# IO_and_MCU.net
KiCad netlist of a schematic drawn in Altium Designer
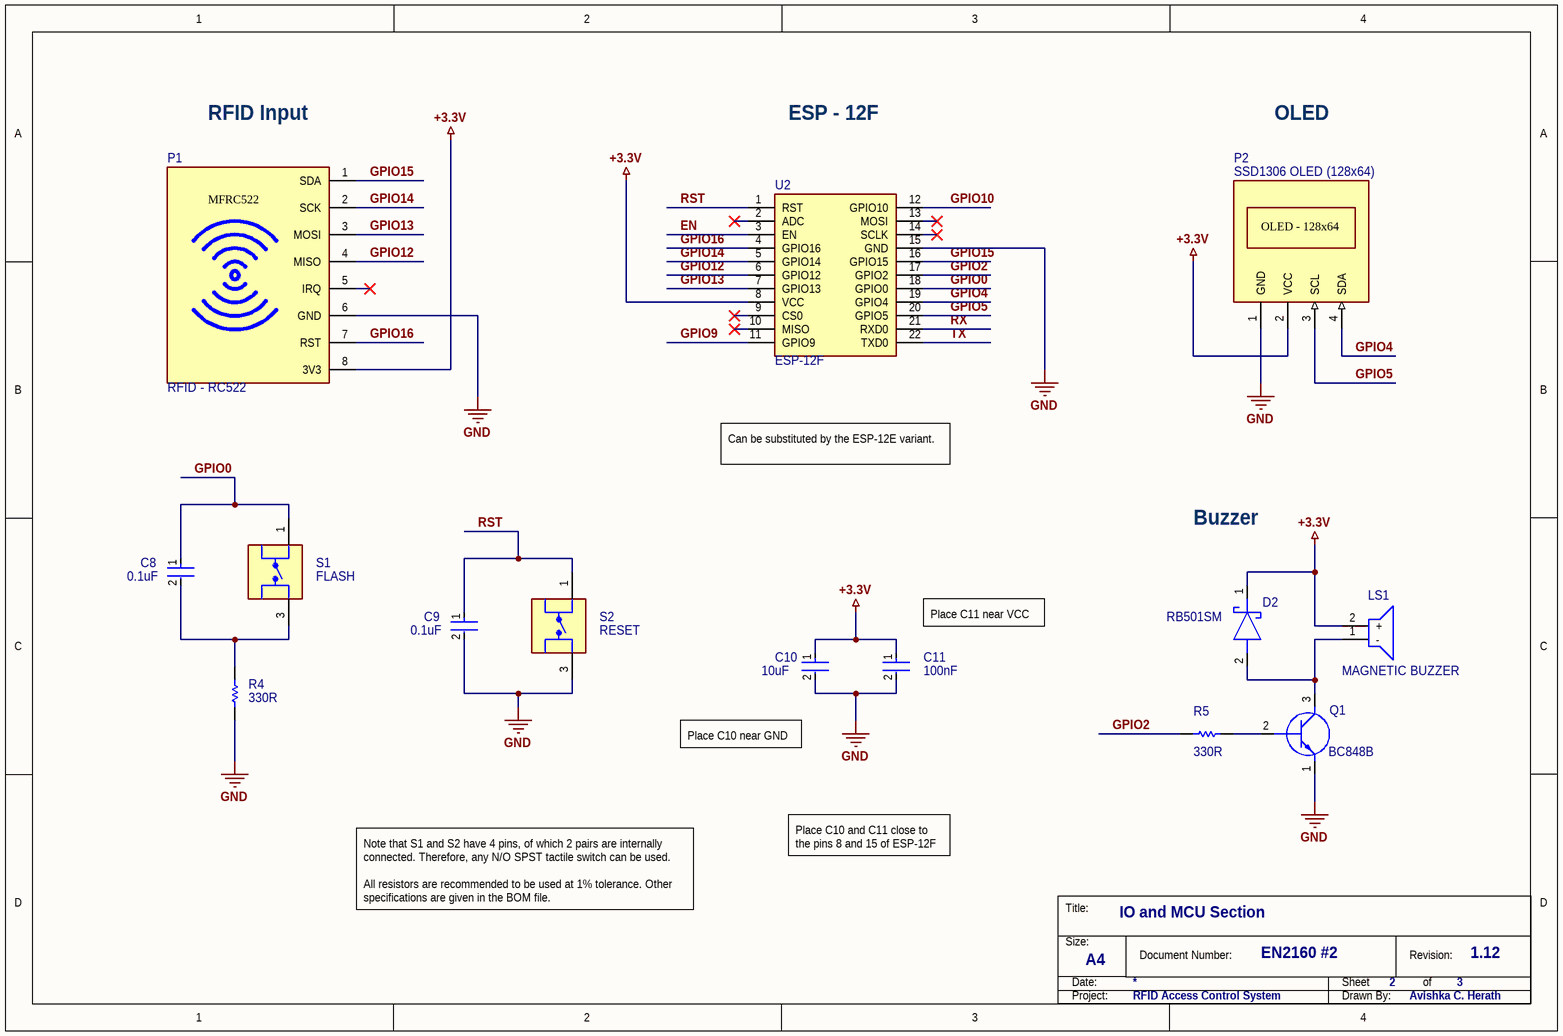
[diagram p0: IO and MCU.SchDoc]

(export (version "E")
  (design (tool "Eeschema 10.0.6"))
  (components
    (comp (ref "C8")
      (value "0.1uF")
      (footprint "FP-CL10-0_1-MFG")
      (description "CAP CER 0.1UF 50V X7R 0603")
      (fields
        (field (name "MANUFACTURER") "Samsung Electro-Mechanics America, Inc")
        (field (name "MANUFACTURER PART NUMBER") "CL10B104JB8NNNC")
      )
      (libsource (lib "Altium Content Vault") (part "b4654b650e69147ec39a6b967a45e02"))
    )
    (comp (ref "C9")
      (value "0.1uF")
      (footprint "FP-CL10-0_1-MFG")
      (description "CAP CER 0.1UF 50V X7R 0603")
      (fields
        (field (name "MANUFACTURER") "Samsung Electro-Mechanics America, Inc")
        (field (name "MANUFACTURER PART NUMBER") "CL10B104JB8NNNC")
      )
      (libsource (lib "Altium Content Vault") (part "b4654b650e69147ec39a6b967a45e02"))
    )
    (comp (ref "C10")
      (value "10uF")
      (footprint "FP-CL21-IPC_B")
      (description "CL21 Series 0805 10uF 16V ±10% Tolerance X5R Multilayer Ceramic Chip Capacitor")
      (fields (field (name "VOLTAGE") "16V") (field (name "TOLERANCE") "10%"))
      (libsource (lib "Altium Content Vault") (part "b4654b650e69147ec39a6b967a45e02"))
    )
    (comp (ref "C11")
      (value "100nF")
      (footprint "FP-CL10-0_1-MFG")
      (description "CAP CER 0.1UF 50V X7R 0603")
      (fields
        (field (name "MANUFACTURER") "Samsung Electro-Mechanics America, Inc")
        (field (name "MANUFACTURER PART NUMBER") "CL10B104JB8NNNC")
      )
      (libsource (lib "Altium Content Vault") (part "b4654b650e69147ec39a6b967a45e02"))
    )
    (comp (ref "D2")
      (value "RB501SM")
      (footprint "SamacSys:RB501SM30FHT2R")
      (description "Schottky Diode")
      (fields
        (field (name "MANUFACTURER_PART_NUMBER") "RB501SM-30FHT2R")
        (field (name "MOUSER PART NUMBER") "755-RB501SM-30FHT2R")
      )
      (libsource (lib "*") (part "RB501SM-30FHT2R"))
    )
    (comp (ref "LS1")
      (value "MAGNETIC BUZZER")
      (footprint "SamacSys:CMI1295IC0385T")
      (description "Loudspeaker or Buzzer")
      (fields
        (field (name "MANUFACTURER_PART_NUMBER") "CMI-1295IC-0385T")
        (field (name "MOUSER PART NUMBER") "490-CMI-1295IC-0385T")
      )
      (libsource (lib "*") (part "CMI-1295IC-0385T"))
    )
    (comp (ref "P1")
      (value "RFID - RC522")
      (footprint "RFID - RC522-Footprint-1")
      (libsource (lib "University of Moratuwa") (part "RFID - RC522"))
    )
    (comp (ref "P2")
      (value "SSD1306 OLED (128x64)")
      (footprint "SSD1306 OLED (128x64)-Footprint-1")
      (libsource (lib "University of Moratuwa") (part "SSD1306 OLED (128x64)"))
    )
    (comp (ref "Q1")
      (value "BC848B")
      (footprint "SamacSys:SOT95P240X120-3N")
      (description "Transistor BJT NPN")
      (fields
        (field (name "MANUFACTURER_PART_NUMBER") "BC848BHZGT116")
        (field (name "MOUSER PART NUMBER") "755-BC848BHZGT116")
      )
      (libsource (lib "*") (part "BC848BHZGT116"))
    )
    (comp (ref "R4")
      (value "330R")
      (footprint "RESC2013X60X35ML10T20")
      (description "Res Thick Film 0805 330R Ohm 1% 0.125W(1/8W) +/-100ppm/C Epoxy Pad SMD T/R")
      (libsource (lib "University of Moratuwa") (part "RES-2"))
    )
    (comp (ref "R5")
      (value "330R")
      (footprint "RESC2013X60X35ML10T20")
      (description "Res Thick Film 0805 330R Ohm 1% 0.125W(1/8W) +/-100ppm/C Epoxy Pad SMD T/R")
      (libsource (lib "University of Moratuwa") (part "RES-2"))
    )
    (comp (ref "S1")
      (value "FLASH")
      (footprint "SW_PTS525SM15SMTR2LFS")
      (description "Tactile Switch SPST-NO Top Actuated Surface Mount")
      (fields (field (name "MP") "PTS525SM15SMTR2 LFS") (field (name "MF") "C&K"))
      (libsource (lib "University of Moratuwa") (part "PTS525SM15SMTR2LFS"))
    )
    (comp (ref "S2")
      (value "RESET")
      (footprint "SW_PTS525SM15SMTR2LFS")
      (description "Tactile Switch SPST-NO Top Actuated Surface Mount")
      (fields (field (name "MP") "PTS525SM15SMTR2 LFS") (field (name "MF") "C&K"))
      (libsource (lib "University of Moratuwa") (part "PTS525SM15SMTR2LFS"))
    )
    (comp (ref "U2")
      (value "ESP-12F")
      (footprint "SamacSys:esp12f")
      (description "Integrated Circuit")
      (libsource (lib "*") (part "esp-12f"))
    )
  )
  (nets
    (net (code "1") (name "+3.3V") (class "Default")
      (node (ref "C10") (pin "1") (pinfunction "1_1") (pintype "passive"))
      (node (ref "C11") (pin "1") (pinfunction "1_1") (pintype "passive"))
      (node (ref "D2") (pin "1") (pinfunction "K_1") (pintype "passive"))
      (node (ref "LS1") (pin "2") (pinfunction "+_2") (pintype "passive"))
      (node (ref "P1") (pin "8") (pinfunction "3V3_8") (pintype "passive"))
      (node (ref "P2") (pin "2") (pinfunction "VCC_2") (pintype "power_in"))
      (node (ref "U2") (pin "8") (pinfunction "VCC_8") (pintype "passive"))
    )
    (net (code "2") (name "/EN") (class "Default")
      (node (ref "U2") (pin "3") (pinfunction "EN_3") (pintype "passive"))
    )
    (net (code "3") (name "/GPIO0") (class "Default")
      (node (ref "C8") (pin "1") (pinfunction "1_1") (pintype "passive"))
      (node (ref "S1") (pin "1") (pinfunction "1_1") (pintype "passive"))
      (node (ref "U2") (pin "18") (pinfunction "GPIO0_18") (pintype "passive"))
    )
    (net (code "4") (name "/GPIO2") (class "Default")
      (node (ref "R5") (pin "1") (pinfunction "1_1") (pintype "passive"))
      (node (ref "U2") (pin "17") (pinfunction "GPIO2_17") (pintype "passive"))
    )
    (net (code "5") (name "/GPIO4") (class "Default")
      (node (ref "P2") (pin "4") (pinfunction "SDA_4") (pintype "input"))
      (node (ref "U2") (pin "19") (pinfunction "GPIO4_19") (pintype "passive"))
    )
    (net (code "6") (name "/GPIO5") (class "Default")
      (node (ref "P2") (pin "3") (pinfunction "SCL_3") (pintype "input"))
      (node (ref "U2") (pin "20") (pinfunction "GPIO5_20") (pintype "passive"))
    )
    (net (code "7") (name "/GPIO9") (class "Default")
      (node (ref "U2") (pin "11") (pinfunction "GPIO9_11") (pintype "passive"))
    )
    (net (code "8") (name "/GPIO10") (class "Default")
      (node (ref "U2") (pin "12") (pinfunction "GPIO10_12") (pintype "passive"))
    )
    (net (code "9") (name "/GPIO12") (class "Default")
      (node (ref "P1") (pin "4") (pinfunction "MISO_4") (pintype "passive"))
      (node (ref "U2") (pin "6") (pinfunction "GPIO12_6") (pintype "passive"))
    )
    (net (code "10") (name "/GPIO13") (class "Default")
      (node (ref "P1") (pin "3") (pinfunction "MOSI_3") (pintype "passive"))
      (node (ref "U2") (pin "7") (pinfunction "GPIO13_7") (pintype "passive"))
    )
    (net (code "11") (name "/GPIO14") (class "Default")
      (node (ref "P1") (pin "2") (pinfunction "SCK_2") (pintype "passive"))
      (node (ref "U2") (pin "5") (pinfunction "GPIO14_5") (pintype "passive"))
    )
    (net (code "12") (name "/GPIO15") (class "Default")
      (node (ref "P1") (pin "1") (pinfunction "SDA_1") (pintype "passive"))
      (node (ref "U2") (pin "16") (pinfunction "GPIO15_16") (pintype "passive"))
    )
    (net (code "13") (name "/GPIO16") (class "Default")
      (node (ref "P1") (pin "7") (pinfunction "RST_7") (pintype "passive"))
      (node (ref "U2") (pin "4") (pinfunction "GPIO16_4") (pintype "passive"))
    )
    (net (code "14") (name "/RST") (class "Default")
      (node (ref "C9") (pin "1") (pinfunction "1_1") (pintype "passive"))
      (node (ref "S2") (pin "1") (pinfunction "1_1") (pintype "passive"))
      (node (ref "U2") (pin "1") (pinfunction "RST_1") (pintype "passive"))
    )
    (net (code "15") (name "/RX") (class "Default")
      (node (ref "U2") (pin "21") (pinfunction "RXD0_21") (pintype "passive"))
    )
    (net (code "16") (name "/TX") (class "Default")
      (node (ref "U2") (pin "22") (pinfunction "TXD0_22") (pintype "passive"))
    )
    (net (code "17") (name "GND") (class "Default")
      (node (ref "C10") (pin "2") (pinfunction "2_2") (pintype "passive"))
      (node (ref "C11") (pin "2") (pinfunction "2_2") (pintype "passive"))
      (node (ref "C9") (pin "2") (pinfunction "2_2") (pintype "passive"))
      (node (ref "P1") (pin "6") (pinfunction "GND_6") (pintype "passive"))
      (node (ref "P2") (pin "1") (pinfunction "GND_1") (pintype "power_in"))
      (node (ref "Q1") (pin "1") (pinfunction "E_1") (pintype "passive"))
      (node (ref "R4") (pin "2") (pinfunction "2_2") (pintype "passive"))
      (node (ref "S2") (pin "3") (pinfunction "3_3") (pintype "passive"))
      (node (ref "U2") (pin "15") (pinfunction "GND_15") (pintype "passive"))
    )
    (net (code "18") (name "Net-(C8-Pad2)") (class "Default")
      (node (ref "C8") (pin "2") (pinfunction "2_2") (pintype "passive"))
      (node (ref "R4") (pin "1") (pinfunction "1_1") (pintype "passive"))
      (node (ref "S1") (pin "3") (pinfunction "3_3") (pintype "passive"))
    )
    (net (code "19") (name "Net-(D2-A)") (class "Default")
      (node (ref "D2") (pin "2") (pinfunction "A_2") (pintype "passive"))
      (node (ref "LS1") (pin "1") (pinfunction "-_1") (pintype "passive"))
      (node (ref "Q1") (pin "3") (pinfunction "C_3") (pintype "passive"))
    )
    (net (code "20") (name "Net-(Q1-B)") (class "Default")
      (node (ref "Q1") (pin "2") (pinfunction "B_2") (pintype "passive"))
      (node (ref "R5") (pin "2") (pinfunction "2_2") (pintype "passive"))
    )
    (net (code "21") (name "unconnected-(P1-IRQ-Pad5)") (class "Default")
      (node (ref "P1") (pin "5") (pinfunction "IRQ_5") (pintype "passive+no_connect"))
    )
    (net (code "22") (name "unconnected-(S1-Pad2)") (class "Default")
      (node (ref "S1") (pin "2") (pinfunction "2_2") (pintype "passive"))
    )
    (net (code "23") (name "unconnected-(S1-Pad4)") (class "Default")
      (node (ref "S1") (pin "4") (pinfunction "4_4") (pintype "passive"))
    )
    (net (code "24") (name "unconnected-(S2-Pad2)") (class "Default")
      (node (ref "S2") (pin "2") (pinfunction "2_2") (pintype "passive"))
    )
    (net (code "25") (name "unconnected-(S2-Pad4)") (class "Default")
      (node (ref "S2") (pin "4") (pinfunction "4_4") (pintype "passive"))
    )
    (net (code "26") (name "unconnected-(U2-ADC-Pad2)") (class "Default")
      (node (ref "U2") (pin "2") (pinfunction "ADC_2") (pintype "passive+no_connect"))
    )
    (net (code "27") (name "unconnected-(U2-CS0-Pad9)") (class "Default")
      (node (ref "U2") (pin "9") (pinfunction "CS0_9") (pintype "passive+no_connect"))
    )
    (net (code "28") (name "unconnected-(U2-MISO-Pad10)") (class "Default")
      (node (ref "U2") (pin "10") (pinfunction "MISO_10") (pintype "passive+no_connect"))
    )
    (net (code "29") (name "unconnected-(U2-MOSI-Pad13)") (class "Default")
      (node (ref "U2") (pin "13") (pinfunction "MOSI_13") (pintype "passive+no_connect"))
    )
    (net (code "30") (name "unconnected-(U2-SCLK-Pad14)") (class "Default")
      (node (ref "U2") (pin "14") (pinfunction "SCLK_14") (pintype "passive+no_connect"))
    )
  )
)
